# antenna_board.net
KiCad netlist of a schematic drawn in Altium Designer
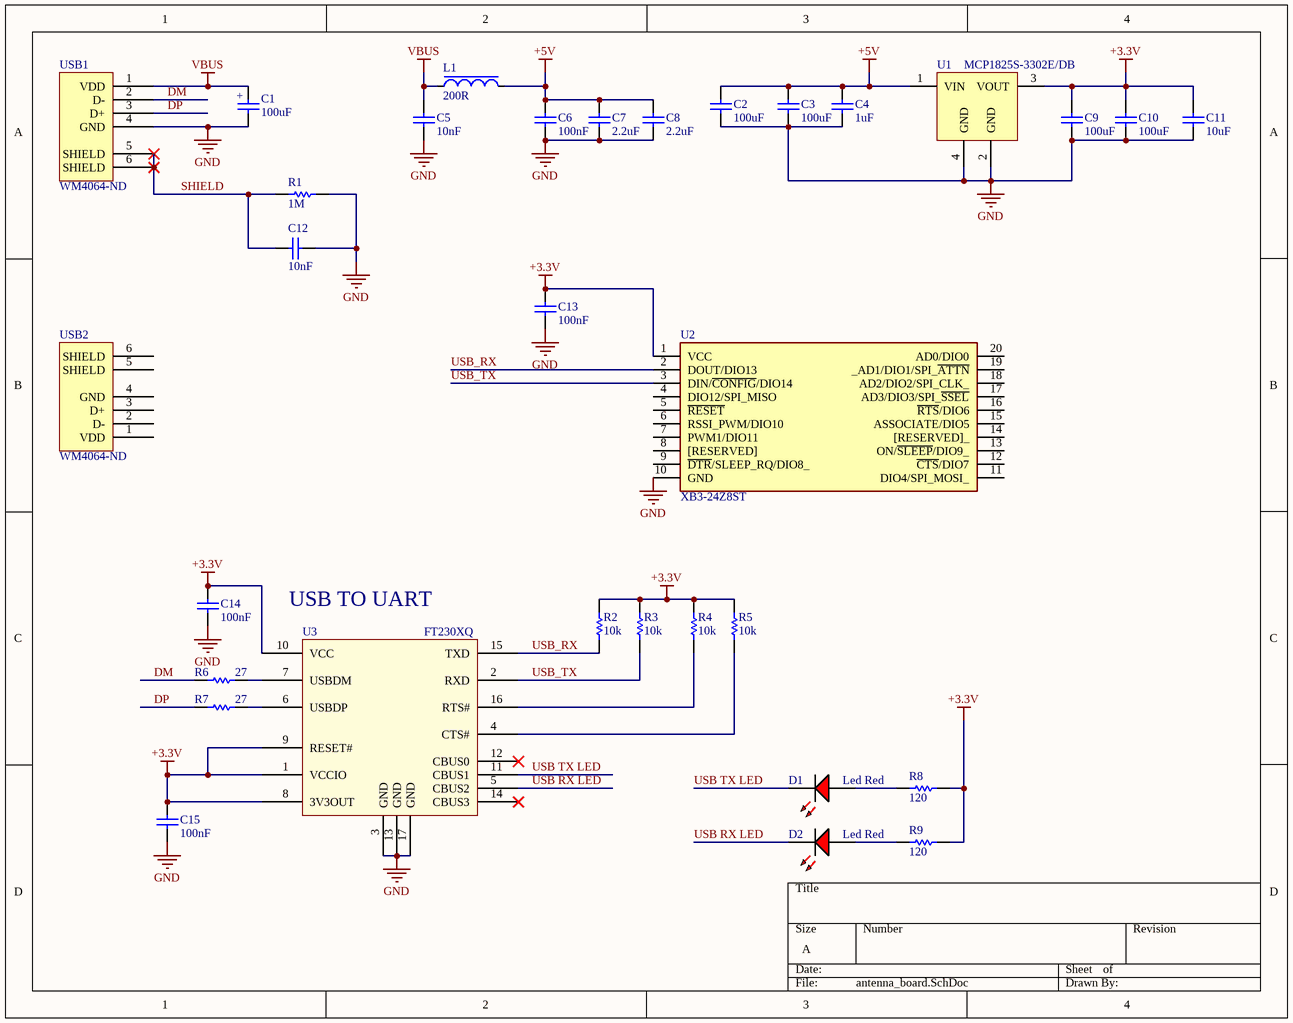
[diagram p0: antenna_board.SchDoc]

(export (version "E")
  (design (tool "Eeschema 10.0.6"))
  (components
    (comp (ref "C1")
      (value "100uF")
      (footprint "CapAlu6.3mmx12.5mm")
      (description "Capacitor 35v 100uF 6.3mm")
      (fields
        (field (name "MANUFACTURER") "Nichicon")
        (field (name "MANUFACTURER PART NUMBER") "UHV1V101MED")
      )
      (libsource (lib "Capacitors") (part "100uF_35v_6.3x12.5"))
    )
    (comp (ref "C2")
      (value "100uF")
      (footprint "CAP_1206")
      (description "CAP CER 100UF 6.3V X5R 1206")
      (fields
        (field (name "MANUFACTURER") "Murata Electronics North America")
        (field (name "MANUFACTURER PART NUMBER") "GRM31CR60J107ME39L")
      )
      (libsource (lib "Capacitors") (part "100uF_6.3v_1206_X5R"))
    )
    (comp (ref "C3")
      (value "100uF")
      (footprint "CAP_1206")
      (description "CAP CER 100UF 6.3V X5R 1206")
      (fields
        (field (name "MANUFACTURER") "Murata Electronics North America")
        (field (name "MANUFACTURER PART NUMBER") "GRM31CR60J107ME39L")
      )
      (libsource (lib "Capacitors") (part "100uF_6.3v_1206_X5R"))
    )
    (comp (ref "C4")
      (value "1uF")
      (footprint "CAP_0402_M")
      (description "CAP CER 1UF 25V 10% X5R 0402")
      (fields
        (field (name "MANUFACTURER") "TDK Corporation")
        (field (name "MANUFACTURER PART NUMBER") "C1005X5R1E105K050BC")
      )
      (libsource (lib "Capacitors") (part "1uF_25V_0402"))
    )
    (comp (ref "C5")
      (value "10nF")
      (footprint "CAP_0402_M")
      (description "CAP CER 10000PF 50V 10% X7R 0402")
      (fields
        (field (name "MANUFACTURER") "Kemet")
        (field (name "MANUFACTURER PART NUMBER") "C0402C103K5RACTU")
      )
      (libsource (lib "Capacitors") (part "10nF_50V_0402"))
    )
    (comp (ref "C6")
      (value "100nF")
      (footprint "CAP_0402_M")
      (description "CAP CER 100NF 50V 20% X5R 0402")
      (fields
        (field (name "MANUFACTURER") "TDK Corporation")
        (field (name "MANUFACTURER PART NUMBER") "C1005X5R1H104M050BB")
      )
      (libsource (lib "Capacitors") (part "100nF_50V_0402"))
    )
    (comp (ref "C7")
      (value "2.2uF")
      (footprint "CAP_0402_M")
      (description "CAP CER 2.2UF 10V 20% X5R 0402")
      (fields
        (field (name "MANUFACTURER") "Taiyo Yuden")
        (field (name "MANUFACTURER PART NUMBER") "LMK105BJ225MV-F")
      )
      (libsource (lib "Capacitors") (part "2.2uF_10V_0402"))
    )
    (comp (ref "C8")
      (value "2.2uF")
      (footprint "CAP_0402_M")
      (description "CAP CER 2.2UF 10V 20% X5R 0402")
      (fields
        (field (name "MANUFACTURER") "Taiyo Yuden")
        (field (name "MANUFACTURER PART NUMBER") "LMK105BJ225MV-F")
      )
      (libsource (lib "Capacitors") (part "2.2uF_10V_0402"))
    )
    (comp (ref "C9")
      (value "100uF")
      (footprint "CAP_1206")
      (description "CAP CER 100UF 6.3V X5R 1206")
      (fields
        (field (name "MANUFACTURER") "Murata Electronics North America")
        (field (name "MANUFACTURER PART NUMBER") "GRM31CR60J107ME39L")
      )
      (libsource (lib "Capacitors") (part "100uF_6.3v_1206_X5R"))
    )
    (comp (ref "C10")
      (value "100uF")
      (footprint "CAP_1206")
      (description "CAP CER 100UF 6.3V X5R 1206")
      (fields
        (field (name "MANUFACTURER") "Murata Electronics North America")
        (field (name "MANUFACTURER PART NUMBER") "GRM31CR60J107ME39L")
      )
      (libsource (lib "Capacitors") (part "100uF_6.3v_1206_X5R"))
    )
    (comp (ref "C11")
      (value "10uF")
      (footprint "CAP_0603")
      (description "CAP CER 10UF 10V 20% X5R 0603")
      (fields
        (field (name "MANUFACTURER") "Taiyo Yuden")
        (field (name "MANUFACTURER PART NUMBER") "LMK107BBJ106MAHT")
      )
      (libsource (lib "Capacitors") (part "10uF_10V_0603"))
    )
    (comp (ref "C12")
      (value "10nF")
      (footprint "CAP_1206")
      (description "CAP CER 10000PF 500V X7R 1206")
      (fields
        (field (name "MANUFACTURER") "Samsung Electro-Mechanics America, Inc")
        (field (name "MANUFACTURER PART NUMBER") "CL31B103KGFNNNE")
      )
      (libsource (lib "Capacitors") (part "10nF_500V_1206"))
    )
    (comp (ref "C13")
      (value "100nF")
      (footprint "CAP_0402_M")
      (description "CAP CER 100NF 50V 20% X5R 0402")
      (fields
        (field (name "MANUFACTURER") "TDK Corporation")
        (field (name "MANUFACTURER PART NUMBER") "C1005X5R1H104M050BB")
      )
      (libsource (lib "Capacitors") (part "100nF_50V_0402"))
    )
    (comp (ref "C14")
      (value "100nF")
      (footprint "CAP_0402_M")
      (description "CAP CER 100NF 50V 20% X5R 0402")
      (fields
        (field (name "MANUFACTURER") "TDK Corporation")
        (field (name "MANUFACTURER PART NUMBER") "C1005X5R1H104M050BB")
      )
      (libsource (lib "Capacitors") (part "100nF_50V_0402"))
    )
    (comp (ref "C15")
      (value "100nF")
      (footprint "CAP_0402_M")
      (description "CAP CER 100NF 50V 20% X5R 0402")
      (fields
        (field (name "MANUFACTURER") "TDK Corporation")
        (field (name "MANUFACTURER PART NUMBER") "C1005X5R1H104M050BB")
      )
      (libsource (lib "Capacitors") (part "100nF_50V_0402"))
    )
    (comp (ref "D1")
      (value "Led Red")
      (footprint "TOPLED 0805")
      (description "LED TOPLED 630NM SUP RED CLR SMD")
      (fields
        (field (name "MANUFACTURER") "OSRAM Opto Semiconductors Inc")
        (field (name "MANUFACTURER PART NUMBER") "LS M67K-H2L1-1-Z")
      )
      (libsource (lib "Diodes") (part "TOPLED 0803"))
    )
    (comp (ref "D2")
      (value "Led Red")
      (footprint "TOPLED 0805")
      (description "LED TOPLED 630NM SUP RED CLR SMD")
      (fields
        (field (name "MANUFACTURER") "OSRAM Opto Semiconductors Inc")
        (field (name "MANUFACTURER PART NUMBER") "LS M67K-H2L1-1-Z")
      )
      (libsource (lib "Diodes") (part "TOPLED 0803"))
    )
    (comp (ref "L1")
      (value "200R")
      (footprint "IND_0603")
      (description "FILTER CHIP 220 OHM 2A 0603")
      (fields
        (field (name "MANUFACTURER") "Murata Electronics North America")
        (field (name "MANUFACTURER PART NUMBER") "BLM18EG221SN1D")
      )
      (libsource (lib "Inductors") (part "Ferrite_200 ohms_2A"))
    )
    (comp (ref "R1")
      (value "1M")
      (footprint "RES_1206")
      (description "RES SMD 1M OHM 5% 1/4W 1206")
      (fields
        (field (name "MANUFACTURER") "Panasonic Electronic Components")
        (field (name "MANUFACTURER PART NUMBER") "ERJ-8GEYJ105V")
      )
      (libsource (lib "Resistors") (part "1M_5%_1206"))
    )
    (comp (ref "R2")
      (value "10k")
      (footprint "RES_0402_M")
      (description "RES SMD 10K OHM 1% 1/10W 0402")
      (fields
        (field (name "MANUFACTURER") "Panasonic Electronic Components")
        (field (name "MANUFACTURER PART NUMBER") "ERJ-2RKF1002X")
      )
      (libsource (lib "Resistors") (part "10k_1%_0402"))
    )
    (comp (ref "R3")
      (value "10k")
      (footprint "RES_0402_M")
      (description "RES SMD 10K OHM 1% 1/10W 0402")
      (fields
        (field (name "MANUFACTURER") "Panasonic Electronic Components")
        (field (name "MANUFACTURER PART NUMBER") "ERJ-2RKF1002X")
      )
      (libsource (lib "Resistors") (part "10k_1%_0402"))
    )
    (comp (ref "R4")
      (value "10k")
      (footprint "RES_0402_M")
      (description "RES SMD 10K OHM 1% 1/10W 0402")
      (fields
        (field (name "MANUFACTURER") "Panasonic Electronic Components")
        (field (name "MANUFACTURER PART NUMBER") "ERJ-2RKF1002X")
      )
      (libsource (lib "Resistors") (part "10k_1%_0402"))
    )
    (comp (ref "R5")
      (value "10k")
      (footprint "RES_0402_M")
      (description "RES SMD 10K OHM 1% 1/10W 0402")
      (fields
        (field (name "MANUFACTURER") "Panasonic Electronic Components")
        (field (name "MANUFACTURER PART NUMBER") "ERJ-2RKF1002X")
      )
      (libsource (lib "Resistors") (part "10k_1%_0402"))
    )
    (comp (ref "R6")
      (value "27")
      (footprint "RES_0402_M")
      (description "RES SMD 27 OHM 1% 1/10W 0402")
      (fields
        (field (name "MANUFACTURER") "Panasonic Electronic Components")
        (field (name "MANUFACTURER PART NUMBER") "ERJ-2RKF27R0X")
      )
      (libsource (lib "Resistors") (part "27_1%_0402"))
    )
    (comp (ref "R7")
      (value "27")
      (footprint "RES_0402_M")
      (description "RES SMD 27 OHM 1% 1/10W 0402")
      (fields
        (field (name "MANUFACTURER") "Panasonic Electronic Components")
        (field (name "MANUFACTURER PART NUMBER") "ERJ-2RKF27R0X")
      )
      (libsource (lib "Resistors") (part "27_1%_0402"))
    )
    (comp (ref "R8")
      (value "120")
      (footprint "RES_0402_M")
      (description "RES SMD 120 OHM 1% 1/10W 0402")
      (fields
        (field (name "MANUFACTURER") "Panasonic Electronic Components")
        (field (name "MANUFACTURER PART NUMBER") "ERJ-2RKF1200X")
      )
      (libsource (lib "Resistors") (part "120_1%_0402"))
    )
    (comp (ref "R9")
      (value "120")
      (footprint "RES_0402_M")
      (description "RES SMD 120 OHM 1% 1/10W 0402")
      (fields
        (field (name "MANUFACTURER") "Panasonic Electronic Components")
        (field (name "MANUFACTURER PART NUMBER") "ERJ-2RKF1200X")
      )
      (libsource (lib "Resistors") (part "120_1%_0402"))
    )
    (comp (ref "U1")
      (value "MCP1825S-3302E/DB")
      (footprint "SOT230P700X180-4N")
      (description "500 mA, Low Voltage, Low Quiescent Current LDO Regulator")
      (fields (field (name "MANUFACTURER") "Microchip Technology"))
      (libsource (lib "ICs") (part "MCP1825S-3302E/DB"))
    )
    (comp (ref "U2")
      (value "XB3-24Z8ST")
      (footprint "SamacSys:XB324Z8ST")
      (description "Integrated Circuit")
      (fields (field (name "MOUSER2 PART NUMBER") "888-XB3-24Z8ST"))
      (libsource (lib "*") (part "XB3-24Z8ST"))
    )
    (comp (ref "U3")
      (value "FT230XQ")
      (footprint "QFN65P400X400X80_HS-17N")
      (description "IC USB SERIAL BASIC UART 16QFN")
      (fields
        (field (name "MANUFACTURER") "FTDI, Future Technology Devices International Ltd")
        (field (name "MANUFACTURER PART NUMBER") "FT230XQ-R")
      )
      (libsource (lib "ICs") (part "FT230XQ-R"))
    )
    (comp (ref "USB1")
      (value "USB type-B jack")
      (footprint "USB2.5-2H4E")
      (fields (field (name "SUPPLIER PART NUMBER 1") "WM4064-ND"))
      (libsource (lib "Connectors") (part "MOLEX 0670688010"))
    )
    (comp (ref "USB2")
      (value "USB type-B jack")
      (footprint "USB2.5-2H4E")
      (fields (field (name "SUPPLIER PART NUMBER 1") "WM4064-ND"))
      (libsource (lib "Connectors") (part "USB Type-B"))
    )
  )
  (nets
    (net (code "1") (name "+3.3V") (class "Default")
      (node (ref "C10") (pin "1") (pinfunction "1_1") (pintype "passive"))
      (node (ref "C11") (pin "1") (pinfunction "1_1") (pintype "passive"))
      (node (ref "C13") (pin "2") (pinfunction "2_2") (pintype "passive"))
      (node (ref "C14") (pin "2") (pinfunction "2_2") (pintype "passive"))
      (node (ref "C15") (pin "2") (pinfunction "2_2") (pintype "passive"))
      (node (ref "C9") (pin "1") (pinfunction "1_1") (pintype "passive"))
      (node (ref "R2") (pin "2") (pinfunction "2_2") (pintype "passive"))
      (node (ref "R3") (pin "2") (pinfunction "2_2") (pintype "passive"))
      (node (ref "R4") (pin "2") (pinfunction "2_2") (pintype "passive"))
      (node (ref "R5") (pin "2") (pinfunction "2_2") (pintype "passive"))
      (node (ref "R8") (pin "2") (pinfunction "2_2") (pintype "passive"))
      (node (ref "R9") (pin "2") (pinfunction "2_2") (pintype "passive"))
      (node (ref "U1") (pin "3") (pinfunction "VOUT_3") (pintype "power_in"))
      (node (ref "U2") (pin "1") (pinfunction "VCC_1") (pintype "passive"))
      (node (ref "U3") (pin "1") (pinfunction "VCCIO_1") (pintype "passive"))
      (node (ref "U3") (pin "10") (pinfunction "VCC_10") (pintype "passive"))
      (node (ref "U3") (pin "8") (pinfunction "3V3OUT_8") (pintype "passive"))
      (node (ref "U3") (pin "9") (pinfunction "RESET#_9") (pintype "passive"))
    )
    (net (code "2") (name "+5V") (class "Default")
      (node (ref "C2") (pin "1") (pinfunction "1_1") (pintype "passive"))
      (node (ref "C3") (pin "1") (pinfunction "1_1") (pintype "passive"))
      (node (ref "C4") (pin "2") (pinfunction "2_2") (pintype "passive"))
      (node (ref "C6") (pin "2") (pinfunction "2_2") (pintype "passive"))
      (node (ref "C7") (pin "2") (pinfunction "2_2") (pintype "passive"))
      (node (ref "C8") (pin "2") (pinfunction "2_2") (pintype "passive"))
      (node (ref "L1") (pin "2") (pinfunction "2_2") (pintype "passive"))
      (node (ref "U1") (pin "1") (pinfunction "VIN_1") (pintype "power_in"))
    )
    (net (code "3") (name "/DM") (class "Default")
      (node (ref "R6") (pin "1") (pinfunction "1_1") (pintype "passive"))
      (node (ref "USB1") (pin "2") (pinfunction "D-_2") (pintype "passive"))
    )
    (net (code "4") (name "/DP") (class "Default")
      (node (ref "R7") (pin "1") (pinfunction "1_1") (pintype "passive"))
      (node (ref "USB1") (pin "3") (pinfunction "D+_3") (pintype "passive"))
    )
    (net (code "5") (name "/SHIELD") (class "Default")
      (node (ref "C12") (pin "2") (pinfunction "2_2") (pintype "passive"))
      (node (ref "R1") (pin "2") (pinfunction "2_2") (pintype "passive"))
      (node (ref "USB1") (pin "5") (pinfunction "SHIELD_5") (pintype "passive"))
      (node (ref "USB1") (pin "6") (pinfunction "SHIELD_6") (pintype "passive"))
    )
    (net (code "6") (name "/USB RX LED") (class "Default")
      (node (ref "D2") (pin "2") (pinfunction "K_2") (pintype "passive"))
      (node (ref "U3") (pin "5") (pinfunction "CBUS2_5") (pintype "passive"))
    )
    (net (code "7") (name "/USB TX LED") (class "Default")
      (node (ref "D1") (pin "2") (pinfunction "K_2") (pintype "passive"))
      (node (ref "U3") (pin "11") (pinfunction "CBUS1_11") (pintype "passive"))
    )
    (net (code "8") (name "/USB_RX") (class "Default")
      (node (ref "R2") (pin "1") (pinfunction "1_1") (pintype "passive"))
      (node (ref "U2") (pin "2") (pinfunction "DOUT/DIO13_2") (pintype "passive"))
      (node (ref "U3") (pin "15") (pinfunction "TXD_15") (pintype "passive"))
    )
    (net (code "9") (name "/USB_TX") (class "Default")
      (node (ref "R3") (pin "1") (pinfunction "1_1") (pintype "passive"))
      (node (ref "U2") (pin "3") (pinfunction "DIN/~{CONFIG}/DIO14_3") (pintype "passive"))
      (node (ref "U3") (pin "2") (pinfunction "RXD_2") (pintype "passive"))
    )
    (net (code "10") (name "GND") (class "Default")
      (node (ref "C1") (pin "2") (pinfunction "2_2") (pintype "passive"))
      (node (ref "C10") (pin "2") (pinfunction "2_2") (pintype "passive"))
      (node (ref "C11") (pin "2") (pinfunction "2_2") (pintype "passive"))
      (node (ref "C12") (pin "1") (pinfunction "1_1") (pintype "passive"))
      (node (ref "C13") (pin "1") (pinfunction "1_1") (pintype "passive"))
      (node (ref "C14") (pin "1") (pinfunction "1_1") (pintype "passive"))
      (node (ref "C15") (pin "1") (pinfunction "1_1") (pintype "passive"))
      (node (ref "C2") (pin "2") (pinfunction "2_2") (pintype "passive"))
      (node (ref "C3") (pin "2") (pinfunction "2_2") (pintype "passive"))
      (node (ref "C4") (pin "1") (pinfunction "1_1") (pintype "passive"))
      (node (ref "C5") (pin "1") (pinfunction "1_1") (pintype "passive"))
      (node (ref "C6") (pin "1") (pinfunction "1_1") (pintype "passive"))
      (node (ref "C7") (pin "1") (pinfunction "1_1") (pintype "passive"))
      (node (ref "C8") (pin "1") (pinfunction "1_1") (pintype "passive"))
      (node (ref "C9") (pin "2") (pinfunction "2_2") (pintype "passive"))
      (node (ref "R1") (pin "1") (pinfunction "1_1") (pintype "passive"))
      (node (ref "U1") (pin "2") (pinfunction "GND_2") (pintype "power_in"))
      (node (ref "U1") (pin "4") (pinfunction "GND_4") (pintype "power_in"))
      (node (ref "U2") (pin "10") (pinfunction "GND_10") (pintype "passive"))
      (node (ref "U3") (pin "13") (pinfunction "GND_13") (pintype "passive"))
      (node (ref "U3") (pin "17") (pinfunction "GND_17") (pintype "passive"))
      (node (ref "U3") (pin "3") (pinfunction "GND_3") (pintype "passive"))
      (node (ref "USB1") (pin "4") (pinfunction "GND_4") (pintype "power_in"))
    )
    (net (code "11") (name "Net-(D1-A)") (class "Default")
      (node (ref "D1") (pin "1") (pinfunction "A_1") (pintype "passive"))
      (node (ref "R8") (pin "1") (pinfunction "1_1") (pintype "passive"))
    )
    (net (code "12") (name "Net-(D2-A)") (class "Default")
      (node (ref "D2") (pin "1") (pinfunction "A_1") (pintype "passive"))
      (node (ref "R9") (pin "1") (pinfunction "1_1") (pintype "passive"))
    )
    (net (code "13") (name "Net-(U3-CTS#)") (class "Default")
      (node (ref "R5") (pin "1") (pinfunction "1_1") (pintype "passive"))
      (node (ref "U3") (pin "4") (pinfunction "CTS#_4") (pintype "passive"))
    )
    (net (code "14") (name "Net-(U3-RTS#)") (class "Default")
      (node (ref "R4") (pin "1") (pinfunction "1_1") (pintype "passive"))
      (node (ref "U3") (pin "16") (pinfunction "RTS#_16") (pintype "passive"))
    )
    (net (code "15") (name "Net-(U3-USBDM)") (class "Default")
      (node (ref "R6") (pin "2") (pinfunction "2_2") (pintype "passive"))
      (node (ref "U3") (pin "7") (pinfunction "USBDM_7") (pintype "passive"))
    )
    (net (code "16") (name "Net-(U3-USBDP)") (class "Default")
      (node (ref "R7") (pin "2") (pinfunction "2_2") (pintype "passive"))
      (node (ref "U3") (pin "6") (pinfunction "USBDP_6") (pintype "passive"))
    )
    (net (code "17") (name "VBUS") (class "Default")
      (node (ref "C1") (pin "1") (pinfunction "1_1") (pintype "passive"))
      (node (ref "C5") (pin "2") (pinfunction "2_2") (pintype "passive"))
      (node (ref "L1") (pin "1") (pinfunction "1_1") (pintype "passive"))
      (node (ref "USB1") (pin "1") (pinfunction "VDD_1") (pintype "power_in"))
    )
    (net (code "18") (name "unconnected-(U2-AD0{slash}DIO0-Pad20)") (class "Default")
      (node (ref "U2") (pin "20") (pinfunction "AD0/DIO0_20") (pintype "passive"))
    )
    (net (code "19") (name "unconnected-(U2-AD2{slash}DIO2{slash}SPI_CLK_-Pad18)") (class "Default")
      (node (ref "U2") (pin "18") (pinfunction "AD2/DIO2/SPI_CLK__18") (pintype "passive"))
    )
    (net (code "20") (name "unconnected-(U2-AD3{slash}DIO3{slash}SPI_~{SSEL}-Pad17)") (class "Default")
      (node (ref "U2") (pin "17") (pinfunction "AD3/DIO3/SPI_~{SSEL}_17") (pintype "passive"))
    )
    (net (code "21") (name "unconnected-(U2-ASSOCIATE{slash}DIO5-Pad15)") (class "Default")
      (node (ref "U2") (pin "15") (pinfunction "ASSOCIATE/DIO5_15") (pintype "passive"))
    )
    (net (code "22") (name "unconnected-(U2-DIO4{slash}SPI_MOSI_-Pad11)") (class "Default")
      (node (ref "U2") (pin "11") (pinfunction "DIO4/SPI_MOSI__11") (pintype "passive"))
    )
    (net (code "23") (name "unconnected-(U2-DIO12{slash}SPI_MISO-Pad4)") (class "Default")
      (node (ref "U2") (pin "4") (pinfunction "DIO12/SPI_MISO_4") (pintype "passive"))
    )
    (net (code "24") (name "unconnected-(U2-ON{slash}~{SLEEP}{slash}DIO9_-Pad13)") (class "Default")
      (node (ref "U2") (pin "13") (pinfunction "ON/~{SLEEP}/DIO9__13") (pintype "passive"))
    )
    (net (code "25") (name "unconnected-(U2-PWM1{slash}DIO11-Pad7)") (class "Default")
      (node (ref "U2") (pin "7") (pinfunction "PWM1/DIO11_7") (pintype "passive"))
    )
    (net (code "26") (name "unconnected-(U2-RSSI_PWM{slash}DIO10-Pad6)") (class "Default")
      (node (ref "U2") (pin "6") (pinfunction "RSSI_PWM/DIO10_6") (pintype "passive"))
    )
    (net (code "27") (name "unconnected-(U2-[RESERVED]-Pad8)") (class "Default")
      (node (ref "U2") (pin "8") (pinfunction "[RESERVED]_8") (pintype "passive"))
    )
    (net (code "28") (name "unconnected-(U2-[RESERVED]_-Pad14)") (class "Default")
      (node (ref "U2") (pin "14") (pinfunction "[RESERVED]__14") (pintype "passive"))
    )
    (net (code "29") (name "unconnected-(U2-_AD1{slash}DIO1{slash}SPI_~{ATTN}-Pad19)") (class "Default")
      (node (ref "U2") (pin "19") (pinfunction "_AD1/DIO1/SPI_~{ATTN}_19") (pintype "passive"))
    )
    (net (code "30") (name "unconnected-(U2-~{CTS}{slash}DIO7-Pad12)") (class "Default")
      (node (ref "U2") (pin "12") (pinfunction "~{CTS}/DIO7_12") (pintype "passive"))
    )
    (net (code "31") (name "unconnected-(U2-~{DTR}{slash}SLEEP_RQ{slash}DIO8_-Pad9)") (class "Default")
      (node (ref "U2") (pin "9") (pinfunction "~{DTR}/SLEEP_RQ/DIO8__9") (pintype "passive"))
    )
    (net (code "32") (name "unconnected-(U2-~{RESET}-Pad5)") (class "Default")
      (node (ref "U2") (pin "5") (pinfunction "~{RESET}_5") (pintype "passive"))
    )
    (net (code "33") (name "unconnected-(U2-~{RTS}{slash}DIO6-Pad16)") (class "Default")
      (node (ref "U2") (pin "16") (pinfunction "~{RTS}/DIO6_16") (pintype "passive"))
    )
    (net (code "34") (name "unconnected-(U3-CBUS0-Pad12)") (class "Default")
      (node (ref "U3") (pin "12") (pinfunction "CBUS0_12") (pintype "passive+no_connect"))
    )
    (net (code "35") (name "unconnected-(U3-CBUS3-Pad14)") (class "Default")
      (node (ref "U3") (pin "14") (pinfunction "CBUS3_14") (pintype "passive+no_connect"))
    )
    (net (code "36") (name "unconnected-(USB2-D+-Pad3)") (class "Default")
      (node (ref "USB2") (pin "3") (pinfunction "D+_3") (pintype "passive"))
    )
    (net (code "37") (name "unconnected-(USB2-D--Pad2)") (class "Default")
      (node (ref "USB2") (pin "2") (pinfunction "D-_2") (pintype "passive"))
    )
    (net (code "38") (name "unconnected-(USB2-GND-Pad4)") (class "Default")
      (node (ref "USB2") (pin "4") (pinfunction "GND_4") (pintype "power_in"))
    )
    (net (code "39") (name "unconnected-(USB2-SHIELD-Pad5)") (class "Default")
      (node (ref "USB2") (pin "5") (pinfunction "SHIELD_5") (pintype "passive"))
    )
    (net (code "40") (name "unconnected-(USB2-SHIELD-Pad6)") (class "Default")
      (node (ref "USB2") (pin "6") (pinfunction "SHIELD_6") (pintype "passive"))
    )
    (net (code "41") (name "unconnected-(USB2-VDD-Pad1)") (class "Default")
      (node (ref "USB2") (pin "1") (pinfunction "VDD_1") (pintype "power_in"))
    )
  )
)
